# ac-adapter.net
KiCad netlist of a schematic drawn in EAGLE
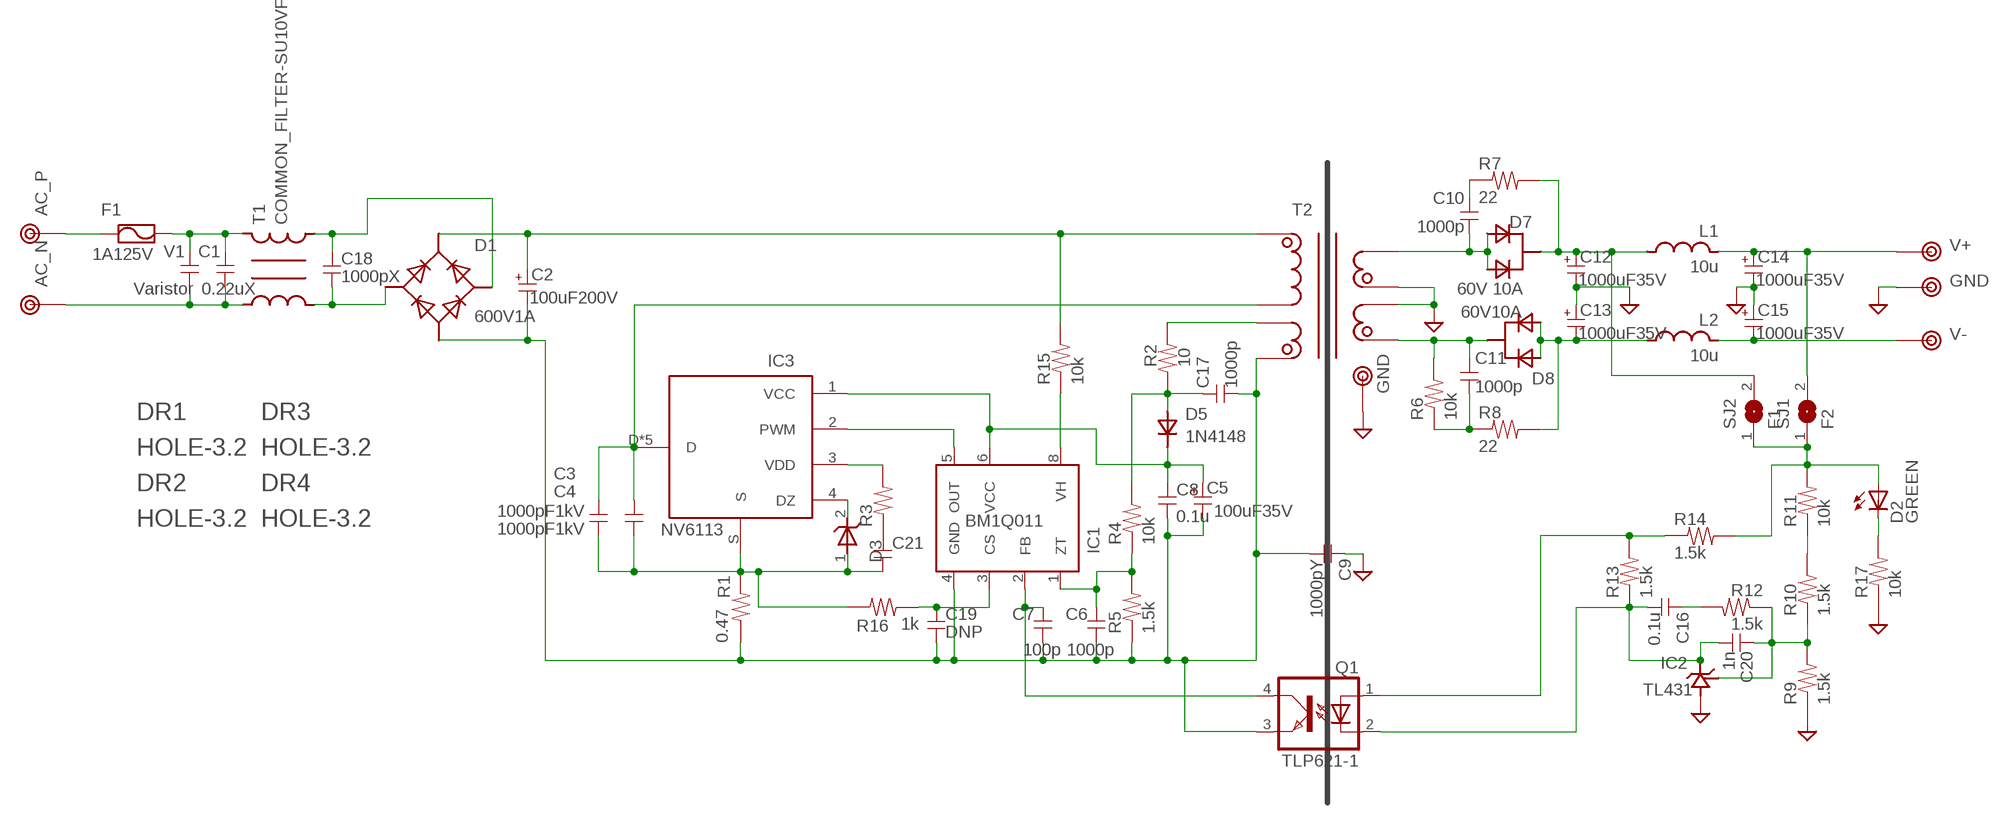
[diagram p0: schematic, sheet 1]

(export (version "E")
  (design (tool "Eeschema 10.0.6"))
  (components
    (comp (ref "C1")
      (value "0.22uX")
      (footprint "eagle-import:X-CAPACITER")
      (libsource (lib "eagle-import") (part "C-X"))
    )
    (comp (ref "C2")
      (value "100uF200V")
      (footprint "eagle-import:E5-16A2")
      (libsource (lib "eagle-import") (part "CPOLE7.5-16A2"))
    )
    (comp (ref "C3")
      (value "1000pF1kV")
      (footprint "eagle-import:C050")
      (libsource (lib "eagle-import") (part "C-5"))
    )
    (comp (ref "C4")
      (value "1000pF1kV")
      (footprint "eagle-import:C050")
      (libsource (lib "eagle-import") (part "C-5"))
    )
    (comp (ref "C5")
      (value "100uF35V")
      (footprint "eagle-import:E2,5-8")
      (libsource (lib "eagle-import") (part "CPOLE2.5-8"))
    )
    (comp (ref "C6")
      (value "1000p")
      (footprint "eagle-import:1608")
      (libsource (lib "eagle-import") (part "C-1608"))
    )
    (comp (ref "C7")
      (value "100p")
      (footprint "eagle-import:1608")
      (libsource (lib "eagle-import") (part "C-1608"))
    )
    (comp (ref "C8")
      (value "0.1u")
      (footprint "eagle-import:2012")
      (libsource (lib "eagle-import") (part "C-2012"))
    )
    (comp (ref "C9")
      (value "1000pY")
      (footprint "eagle-import:Y-CAPACITER")
      (libsource (lib "eagle-import") (part "C-Y"))
    )
    (comp (ref "C10")
      (value "1000p")
      (footprint "eagle-import:1608")
      (libsource (lib "eagle-import") (part "C-1608"))
    )
    (comp (ref "C11")
      (value "1000p")
      (footprint "eagle-import:1608")
      (libsource (lib "eagle-import") (part "C-1608"))
    )
    (comp (ref "C12")
      (value "1000uF35V")
      (footprint "eagle-import:E5-13")
      (libsource (lib "eagle-import") (part "CPOLE5-13"))
    )
    (comp (ref "C13")
      (value "1000uF35V")
      (footprint "eagle-import:E5-13")
      (libsource (lib "eagle-import") (part "CPOLE5-13"))
    )
    (comp (ref "C14")
      (value "1000uF35V")
      (footprint "eagle-import:E5-10")
      (libsource (lib "eagle-import") (part "CPOLE5-10"))
    )
    (comp (ref "C15")
      (value "1000uF35V")
      (footprint "eagle-import:E5-10")
      (libsource (lib "eagle-import") (part "CPOLE5-10"))
    )
    (comp (ref "C16")
      (value "0.1u")
      (footprint "eagle-import:1608")
      (libsource (lib "eagle-import") (part "C-1608"))
    )
    (comp (ref "C17")
      (value "1000p")
      (footprint "eagle-import:1608")
      (libsource (lib "eagle-import") (part "C-1608"))
    )
    (comp (ref "C18")
      (value "1000pX")
      (footprint "eagle-import:C050")
      (libsource (lib "eagle-import") (part "C-5"))
    )
    (comp (ref "C19")
      (value "DNP")
      (footprint "eagle-import:1608")
      (libsource (lib "eagle-import") (part "C-1608"))
    )
    (comp (ref "C20")
      (value "1n")
      (footprint "eagle-import:1608")
      (libsource (lib "eagle-import") (part "C-1608"))
    )
    (comp (ref "C21")
      (value "C-1608")
      (footprint "eagle-import:1608")
      (libsource (lib "eagle-import") (part "C-1608"))
    )
    (comp (ref "D1")
      (value "600V1A")
      (footprint "eagle-import:GBU8A")
      (libsource (lib "eagle-import") (part "DIODE4-GBU8A"))
    )
    (comp (ref "D2")
      (value "GREEN")
      (footprint "eagle-import:D1608")
      (libsource (lib "eagle-import") (part "LED-SMD1608"))
    )
    (comp (ref "D3")
      (value "ZENER-SMD")
      (footprint "eagle-import:SOD123")
      (libsource (lib "eagle-import") (part "ZENER-SMD"))
    )
    (comp (ref "D5")
      (value "1N4148")
      (footprint "eagle-import:SOD123")
      (libsource (lib "eagle-import") (part "DIODE-1N4148W"))
    )
    (comp (ref "D7")
      (value "60V 10A")
      (footprint "eagle-import:TO-220")
      (libsource (lib "eagle-import") (part "DIODE2"))
    )
    (comp (ref "D8")
      (value "60V10A")
      (footprint "eagle-import:TO-220")
      (libsource (lib "eagle-import") (part "DIODE2"))
    )
    (comp (ref "DR1")
      (value "HOLE-3.2")
      (footprint "eagle-import:HOLE_3.2")
      (libsource (lib "eagle-import") (part "HOLE-3.2"))
    )
    (comp (ref "DR2")
      (value "HOLE-3.2")
      (footprint "eagle-import:HOLE_3.2")
      (libsource (lib "eagle-import") (part "HOLE-3.2"))
    )
    (comp (ref "DR3")
      (value "HOLE-3.2")
      (footprint "eagle-import:HOLE_3.2")
      (libsource (lib "eagle-import") (part "HOLE-3.2"))
    )
    (comp (ref "DR4")
      (value "HOLE-3.2")
      (footprint "eagle-import:HOLE_3.2")
      (libsource (lib "eagle-import") (part "HOLE-3.2"))
    )
    (comp (ref "F1")
      (value "1A125V")
      (footprint "eagle-import:FUSE-5")
      (libsource (lib "eagle-import") (part "FUSE-5"))
    )
    (comp (ref "IC1")
      (value "BM1Q011")
      (footprint "eagle-import:SOP8-J7S")
      (libsource (lib "eagle-import") (part "BM1Q011"))
    )
    (comp (ref "IC2")
      (value "TL431")
      (footprint "eagle-import:TO-92")
      (libsource (lib "eagle-import") (part "TL431"))
    )
    (comp (ref "IC3")
      (value "NV6113")
      (footprint "eagle-import:NV6113")
      (libsource (lib "eagle-import") (part "NV6113"))
    )
    (comp (ref "L1")
      (value "10u")
      (footprint "eagle-import:L5-7,5")
      (libsource (lib "eagle-import") (part "L-5"))
    )
    (comp (ref "L2")
      (value "10u")
      (footprint "eagle-import:L5-7,5")
      (libsource (lib "eagle-import") (part "L-5"))
    )
    (comp (ref "Q1")
      (value "TLP621-1")
      (footprint "eagle-import:DIL04")
      (libsource (lib "eagle-import") (part "TLP621-1"))
    )
    (comp (ref "R1")
      (value "0.47")
      (footprint "eagle-import:0207_10")
      (libsource (lib "eagle-import") (part "R-10"))
    )
    (comp (ref "R2")
      (value "10")
      (footprint "eagle-import:2012")
      (libsource (lib "eagle-import") (part "R-2012"))
    )
    (comp (ref "R3")
      (value "R-1608")
      (footprint "eagle-import:1608")
      (libsource (lib "eagle-import") (part "R-1608"))
    )
    (comp (ref "R4")
      (value "10k")
      (footprint "eagle-import:1608")
      (libsource (lib "eagle-import") (part "R-1608"))
    )
    (comp (ref "R5")
      (value "1.5k")
      (footprint "eagle-import:1608")
      (libsource (lib "eagle-import") (part "R-1608"))
    )
    (comp (ref "R6")
      (value "10k")
      (footprint "eagle-import:1608")
      (libsource (lib "eagle-import") (part "R-1608"))
    )
    (comp (ref "R7")
      (value "22")
      (footprint "eagle-import:2012")
      (libsource (lib "eagle-import") (part "R-2012"))
    )
    (comp (ref "R8")
      (value "22")
      (footprint "eagle-import:2012")
      (libsource (lib "eagle-import") (part "R-2012"))
    )
    (comp (ref "R9")
      (value "1.5k")
      (footprint "eagle-import:1608")
      (libsource (lib "eagle-import") (part "R-1608"))
    )
    (comp (ref "R10")
      (value "1.5k")
      (footprint "eagle-import:1608")
      (libsource (lib "eagle-import") (part "R-1608"))
    )
    (comp (ref "R11")
      (value "10k")
      (footprint "eagle-import:1608")
      (libsource (lib "eagle-import") (part "R-1608"))
    )
    (comp (ref "R12")
      (value "1.5k")
      (footprint "eagle-import:1608")
      (libsource (lib "eagle-import") (part "R-1608"))
    )
    (comp (ref "R13")
      (value "1.5k")
      (footprint "eagle-import:1608")
      (libsource (lib "eagle-import") (part "R-1608"))
    )
    (comp (ref "R14")
      (value "1.5k")
      (footprint "eagle-import:1608")
      (libsource (lib "eagle-import") (part "R-1608"))
    )
    (comp (ref "R15")
      (value "10k")
      (footprint "eagle-import:2012")
      (libsource (lib "eagle-import") (part "R-2012"))
    )
    (comp (ref "R16")
      (value "1k")
      (footprint "eagle-import:1608")
      (libsource (lib "eagle-import") (part "R-1608"))
    )
    (comp (ref "R17")
      (value "10k")
      (footprint "eagle-import:1608")
      (libsource (lib "eagle-import") (part "R-1608"))
    )
    (comp (ref "SJ1")
      (value "F2")
      (footprint "eagle-import:SJ1608")
      (libsource (lib "eagle-import") (part "SJ1608"))
    )
    (comp (ref "SJ2")
      (value "F1")
      (footprint "eagle-import:SJ1608")
      (libsource (lib "eagle-import") (part "SJ1608"))
    )
    (comp (ref "T1")
      (value "COMMON_FILTER-SU10VFC")
      (footprint "eagle-import:SU10VFC")
      (libsource (lib "eagle-import") (part "COMMON_FILTER-SU10VFC"))
    )
    (comp (ref "T2")
      (value "TRANSFORMAER_FLYBACK-PQ2620-2")
      (footprint "eagle-import:BPQ26_20-1112CPFR")
      (libsource (lib "eagle-import") (part "TRANSFORMAER_FLYBACK-PQ2620-2"))
    )
    (comp (ref "TP1")
      (value "AC_P")
      (footprint "eagle-import:TESTPIN-LARGE")
      (libsource (lib "eagle-import") (part "TESTPIN-LARGE"))
    )
    (comp (ref "TP2")
      (value "AC_N")
      (footprint "eagle-import:TESTPIN-LARGE")
      (libsource (lib "eagle-import") (part "TESTPIN-LARGE"))
    )
    (comp (ref "TP3")
      (value "V+")
      (footprint "eagle-import:TESTPIN-LARGE")
      (libsource (lib "eagle-import") (part "TESTPIN-LARGE"))
    )
    (comp (ref "TP4")
      (value "GND")
      (footprint "eagle-import:TESTPIN-LARGE")
      (libsource (lib "eagle-import") (part "TESTPIN-LARGE"))
    )
    (comp (ref "TP5")
      (value "V-")
      (footprint "eagle-import:TESTPIN-LARGE")
      (libsource (lib "eagle-import") (part "TESTPIN-LARGE"))
    )
    (comp (ref "TP6")
      (value "GND")
      (footprint "eagle-import:TESTPIN-BIG")
      (libsource (lib "eagle-import") (part "TESTPIN-BIG"))
    )
    (comp (ref "V1")
      (value "Varistor")
      (footprint "eagle-import:C050")
      (libsource (lib "eagle-import") (part "C-5"))
    )
  )
  (nets
    (net (code "1") (name "GND") (class "Default")
      (node (ref "C12") (pin "-") (pinfunction "2_-") (pintype "passive"))
      (node (ref "C13") (pin "+") (pinfunction "1_+") (pintype "passive"))
      (node (ref "C14") (pin "-") (pinfunction "2_-") (pintype "passive"))
      (node (ref "C15") (pin "+") (pinfunction "1_+") (pintype "passive"))
      (node (ref "C9") (pin "1") (pinfunction "1_1") (pintype "passive"))
      (node (ref "IC2") (pin "2") (pinfunction "GND_2") (pintype "bidirectional"))
      (node (ref "R17") (pin "1") (pinfunction "1_1") (pintype "passive"))
      (node (ref "R9") (pin "1") (pinfunction "1_1") (pintype "passive"))
      (node (ref "T2") (pin "10") (pinfunction "L4_N_10") (pintype "passive"))
      (node (ref "T2") (pin "9") (pinfunction "L3_P_9") (pintype "passive"))
      (node (ref "TP4") (pin "1") (pinfunction "1_1") (pintype "passive"))
      (node (ref "TP6") (pin "1") (pinfunction "1_1") (pintype "passive"))
    )
    (net (code "2") (name "Net-(C1-Pad2)") (class "Default")
      (node (ref "C1") (pin "2") (pinfunction "2_2") (pintype "passive"))
      (node (ref "T1") (pin "1") (pinfunction "1_1") (pintype "passive"))
      (node (ref "TP2") (pin "1") (pinfunction "1_1") (pintype "passive"))
      (node (ref "V1") (pin "2") (pinfunction "2_2") (pintype "passive"))
    )
    (net (code "3") (name "Net-(C2-1)") (class "Default")
      (node (ref "C2") (pin "+") (pinfunction "1_+") (pintype "passive"))
      (node (ref "D1") (pin "1") (pinfunction "V+_1") (pintype "passive"))
      (node (ref "R15") (pin "2") (pinfunction "2_2") (pintype "passive"))
      (node (ref "T2") (pin "3") (pinfunction "L1_P_3") (pintype "passive"))
    )
    (net (code "4") (name "Net-(C2-2)") (class "Default")
      (node (ref "C17") (pin "2") (pinfunction "2_2") (pintype "passive"))
      (node (ref "C19") (pin "2") (pinfunction "2_2") (pintype "passive"))
      (node (ref "C2") (pin "-") (pinfunction "2_-") (pintype "passive"))
      (node (ref "C5") (pin "-") (pinfunction "2_-") (pintype "passive"))
      (node (ref "C6") (pin "2") (pinfunction "2_2") (pintype "passive"))
      (node (ref "C7") (pin "2") (pinfunction "2_2") (pintype "passive"))
      (node (ref "C8") (pin "2") (pinfunction "2_2") (pintype "passive"))
      (node (ref "C9") (pin "2") (pinfunction "2_2") (pintype "passive"))
      (node (ref "D1") (pin "4") (pinfunction "V-_4") (pintype "passive"))
      (node (ref "IC1") (pin "4") (pinfunction "GND_4") (pintype "power_in"))
      (node (ref "Q1") (pin "3") (pinfunction "EMIT_3") (pintype "passive"))
      (node (ref "R1") (pin "1") (pinfunction "1_1") (pintype "passive"))
      (node (ref "R5") (pin "1") (pinfunction "1_1") (pintype "passive"))
      (node (ref "T2") (pin "5") (pinfunction "L2_P_5") (pintype "passive"))
    )
    (net (code "5") (name "Net-(C5-1)") (class "Default")
      (node (ref "C5") (pin "+") (pinfunction "1_+") (pintype "passive"))
      (node (ref "C8") (pin "1") (pinfunction "1_1") (pintype "passive"))
      (node (ref "D5") (pin "2") (pinfunction "K_2") (pintype "passive"))
      (node (ref "IC1") (pin "6") (pinfunction "VCC_6") (pintype "power_in"))
      (node (ref "IC3") (pin "1") (pinfunction "VCC_1") (pintype "power_in"))
    )
    (net (code "6") (name "Net-(C10-Pad1)") (class "Default")
      (node (ref "C10") (pin "1") (pinfunction "1_1") (pintype "passive"))
      (node (ref "R7") (pin "1") (pinfunction "1_1") (pintype "passive"))
    )
    (net (code "7") (name "Net-(C11-Pad2)") (class "Default")
      (node (ref "C11") (pin "2") (pinfunction "2_2") (pintype "passive"))
      (node (ref "R6") (pin "1") (pinfunction "1_1") (pintype "passive"))
      (node (ref "R8") (pin "1") (pinfunction "1_1") (pintype "passive"))
    )
    (net (code "8") (name "Net-(C12-1)") (class "Default")
      (node (ref "C12") (pin "+") (pinfunction "1_+") (pintype "passive"))
      (node (ref "D7") (pin "2") (pinfunction "K_2") (pintype "passive"))
      (node (ref "L1") (pin "2") (pinfunction "1_2") (pintype "passive"))
      (node (ref "R7") (pin "2") (pinfunction "2_2") (pintype "passive"))
      (node (ref "SJ2") (pin "2") (pinfunction "2_2") (pintype "passive"))
    )
    (net (code "9") (name "Net-(C13-2)") (class "Default")
      (node (ref "C13") (pin "-") (pinfunction "2_-") (pintype "passive"))
      (node (ref "D8") (pin "1") (pinfunction "A1_1") (pintype "passive"))
      (node (ref "D8") (pin "3") (pinfunction "A2_3") (pintype "passive"))
      (node (ref "L2") (pin "2") (pinfunction "1_2") (pintype "passive"))
      (node (ref "R8") (pin "2") (pinfunction "2_2") (pintype "passive"))
    )
    (net (code "10") (name "Net-(C14-1)") (class "Default")
      (node (ref "C14") (pin "+") (pinfunction "1_+") (pintype "passive"))
      (node (ref "L1") (pin "1") (pinfunction "2_1") (pintype "passive"))
      (node (ref "SJ1") (pin "2") (pinfunction "2_2") (pintype "passive"))
      (node (ref "TP3") (pin "1") (pinfunction "1_1") (pintype "passive"))
    )
    (net (code "11") (name "Net-(C15-2)") (class "Default")
      (node (ref "C15") (pin "-") (pinfunction "2_-") (pintype "passive"))
      (node (ref "L2") (pin "1") (pinfunction "2_1") (pintype "passive"))
      (node (ref "TP5") (pin "1") (pinfunction "1_1") (pintype "passive"))
    )
    (net (code "12") (name "Net-(C16-Pad1)") (class "Default")
      (node (ref "C16") (pin "1") (pinfunction "1_1") (pintype "passive"))
      (node (ref "R12") (pin "2") (pinfunction "2_2") (pintype "passive"))
    )
    (net (code "13") (name "Net-(C21-Pad1)") (class "Default")
      (node (ref "C21") (pin "1") (pinfunction "1_1") (pintype "passive"))
      (node (ref "R3") (pin "1") (pinfunction "1_1") (pintype "passive"))
    )
    (net (code "14") (name "Net-(D1-AC1)") (class "Default")
      (node (ref "C18") (pin "2") (pinfunction "2_2") (pintype "passive"))
      (node (ref "D1") (pin "2") (pinfunction "AC1_2") (pintype "passive"))
      (node (ref "T1") (pin "2") (pinfunction "2_2") (pintype "passive"))
    )
    (net (code "15") (name "Net-(D1-AC2)") (class "Default")
      (node (ref "C18") (pin "1") (pinfunction "1_1") (pintype "passive"))
      (node (ref "D1") (pin "3") (pinfunction "AC2_3") (pintype "passive"))
      (node (ref "T1") (pin "3") (pinfunction "3_3") (pintype "passive"))
    )
    (net (code "16") (name "Net-(D2-PadA)") (class "Default")
      (node (ref "D2") (pin "A") (pinfunction "A_A") (pintype "passive"))
      (node (ref "R11") (pin "2") (pinfunction "2_2") (pintype "passive"))
      (node (ref "R14") (pin "2") (pinfunction "2_2") (pintype "passive"))
      (node (ref "SJ1") (pin "1") (pinfunction "1_1") (pintype "passive"))
      (node (ref "SJ2") (pin "1") (pinfunction "1_1") (pintype "passive"))
    )
    (net (code "17") (name "Net-(D2-PadK)") (class "Default")
      (node (ref "D2") (pin "K") (pinfunction "K_K") (pintype "passive"))
      (node (ref "R17") (pin "2") (pinfunction "2_2") (pintype "passive"))
    )
    (net (code "18") (name "Net-(D3-A)") (class "Default")
      (node (ref "C21") (pin "2") (pinfunction "2_2") (pintype "passive"))
      (node (ref "C3") (pin "2") (pinfunction "2_2") (pintype "passive"))
      (node (ref "C4") (pin "2") (pinfunction "2_2") (pintype "passive"))
      (node (ref "D3") (pin "1") (pinfunction "A_1") (pintype "bidirectional"))
      (node (ref "IC3") (pin "S") (pinfunction "S_S") (pintype "passive"))
      (node (ref "R1") (pin "2") (pinfunction "2_2") (pintype "passive"))
      (node (ref "R16") (pin "1") (pinfunction "1_1") (pintype "passive"))
    )
    (net (code "19") (name "Net-(D3-C)") (class "Default")
      (node (ref "D3") (pin "2") (pinfunction "C_2") (pintype "bidirectional"))
      (node (ref "IC3") (pin "4") (pinfunction "DZ_4") (pintype "bidirectional"))
    )
    (net (code "20") (name "Net-(D5-A)") (class "Default")
      (node (ref "C17") (pin "1") (pinfunction "1_1") (pintype "passive"))
      (node (ref "D5") (pin "1") (pinfunction "A_1") (pintype "passive"))
      (node (ref "R2") (pin "1") (pinfunction "1_1") (pintype "passive"))
      (node (ref "R4") (pin "2") (pinfunction "2_2") (pintype "passive"))
    )
    (net (code "21") (name "Net-(D7-A1)") (class "Default")
      (node (ref "C10") (pin "2") (pinfunction "2_2") (pintype "passive"))
      (node (ref "D7") (pin "1") (pinfunction "A1_1") (pintype "passive"))
      (node (ref "D7") (pin "3") (pinfunction "A2_3") (pintype "passive"))
      (node (ref "T2") (pin "7") (pinfunction "L3_N_7") (pintype "passive"))
      (node (ref "T2") (pin "8") (pinfunction "L3_N_8") (pintype "passive"))
    )
    (net (code "22") (name "Net-(D8-K)") (class "Default")
      (node (ref "C11") (pin "1") (pinfunction "1_1") (pintype "passive"))
      (node (ref "D8") (pin "2") (pinfunction "K_2") (pintype "passive"))
      (node (ref "R6") (pin "2") (pinfunction "2_2") (pintype "passive"))
      (node (ref "T2") (pin "11") (pinfunction "L4_P_11") (pintype "passive"))
      (node (ref "T2") (pin "12") (pinfunction "L4_P_12") (pintype "passive"))
    )
    (net (code "23") (name "Net-(F1-P$1)") (class "Default")
      (node (ref "F1") (pin "1") (pinfunction "P$1_1") (pintype "passive"))
      (node (ref "TP1") (pin "1") (pinfunction "1_1") (pintype "passive"))
    )
    (net (code "24") (name "Net-(F1-P$2)") (class "Default")
      (node (ref "C1") (pin "1") (pinfunction "1_1") (pintype "passive"))
      (node (ref "F1") (pin "2") (pinfunction "P$2_2") (pintype "passive"))
      (node (ref "T1") (pin "4") (pinfunction "4_4") (pintype "passive"))
      (node (ref "V1") (pin "1") (pinfunction "1_1") (pintype "passive"))
    )
    (net (code "25") (name "Net-(IC1-CS)") (class "Default")
      (node (ref "C19") (pin "1") (pinfunction "1_1") (pintype "passive"))
      (node (ref "IC1") (pin "3") (pinfunction "CS_3") (pintype "input"))
      (node (ref "R16") (pin "2") (pinfunction "2_2") (pintype "passive"))
    )
    (net (code "26") (name "Net-(IC1-FB)") (class "Default")
      (node (ref "C7") (pin "1") (pinfunction "1_1") (pintype "passive"))
      (node (ref "IC1") (pin "2") (pinfunction "FB_2") (pintype "input"))
      (node (ref "Q1") (pin "4") (pinfunction "COL_4") (pintype "passive"))
    )
    (net (code "27") (name "Net-(IC1-OUT)") (class "Default")
      (node (ref "IC1") (pin "5") (pinfunction "OUT_5") (pintype "output"))
      (node (ref "IC3") (pin "2") (pinfunction "PWM_2") (pintype "input"))
    )
    (net (code "28") (name "Net-(IC1-VH)") (class "Default")
      (node (ref "IC1") (pin "8") (pinfunction "VH_8") (pintype "power_in"))
      (node (ref "R15") (pin "1") (pinfunction "1_1") (pintype "passive"))
    )
    (net (code "29") (name "Net-(IC1-ZT)") (class "Default")
      (node (ref "C6") (pin "1") (pinfunction "1_1") (pintype "passive"))
      (node (ref "IC1") (pin "1") (pinfunction "ZT_1") (pintype "input"))
      (node (ref "R4") (pin "1") (pinfunction "1_1") (pintype "passive"))
      (node (ref "R5") (pin "2") (pinfunction "2_2") (pintype "passive"))
    )
    (net (code "30") (name "Net-(IC2-OUT)") (class "Default")
      (node (ref "C16") (pin "2") (pinfunction "2_2") (pintype "passive"))
      (node (ref "C20") (pin "2") (pinfunction "2_2") (pintype "passive"))
      (node (ref "IC2") (pin "3") (pinfunction "OUT_3") (pintype "bidirectional"))
      (node (ref "Q1") (pin "2") (pinfunction "C_2") (pintype "passive"))
      (node (ref "R13") (pin "1") (pinfunction "1_1") (pintype "passive"))
    )
    (net (code "31") (name "Net-(IC2-REF)") (class "Default")
      (node (ref "C20") (pin "1") (pinfunction "1_1") (pintype "passive"))
      (node (ref "IC2") (pin "1") (pinfunction "REF_1") (pintype "input"))
      (node (ref "R10") (pin "1") (pinfunction "1_1") (pintype "passive"))
      (node (ref "R12") (pin "1") (pinfunction "1_1") (pintype "passive"))
      (node (ref "R9") (pin "2") (pinfunction "2_2") (pintype "passive"))
    )
    (net (code "32") (name "Net-(IC3-VDD)") (class "Default")
      (node (ref "IC3") (pin "3") (pinfunction "VDD_3") (pintype "power_in"))
      (node (ref "R3") (pin "2") (pinfunction "2_2") (pintype "passive"))
    )
    (net (code "33") (name "Net-(Q1-A)") (class "Default")
      (node (ref "Q1") (pin "1") (pinfunction "A_1") (pintype "passive"))
      (node (ref "R13") (pin "2") (pinfunction "2_2") (pintype "passive"))
      (node (ref "R14") (pin "1") (pinfunction "1_1") (pintype "passive"))
    )
    (net (code "34") (name "Net-(R10-Pad2)") (class "Default")
      (node (ref "R10") (pin "2") (pinfunction "2_2") (pintype "passive"))
      (node (ref "R11") (pin "1") (pinfunction "1_1") (pintype "passive"))
    )
    (net (code "35") (name "Net-(T2-L1_N)") (class "Default")
      (node (ref "C3") (pin "1") (pinfunction "1_1") (pintype "passive"))
      (node (ref "C4") (pin "1") (pinfunction "1_1") (pintype "passive"))
      (node (ref "IC3") (pin "D") (pinfunction "D_D") (pintype "passive"))
      (node (ref "IC3") (pin "D1") (pinfunction "D_D1") (pintype "passive"))
      (node (ref "IC3") (pin "D2") (pinfunction "D_D2") (pintype "passive"))
      (node (ref "IC3") (pin "D3") (pinfunction "D_D3") (pintype "passive"))
      (node (ref "IC3") (pin "D4") (pinfunction "D_D4") (pintype "passive"))
      (node (ref "T2") (pin "1") (pinfunction "L1_N_1") (pintype "passive"))
    )
    (net (code "36") (name "Net-(T2-L2_N)") (class "Default")
      (node (ref "R2") (pin "2") (pinfunction "2_2") (pintype "passive"))
      (node (ref "T2") (pin "6") (pinfunction "L2_N_6") (pintype "passive"))
    )
  )
)
